# WatchSchematic.net
KiCad netlist of a schematic drawn in EAGLE
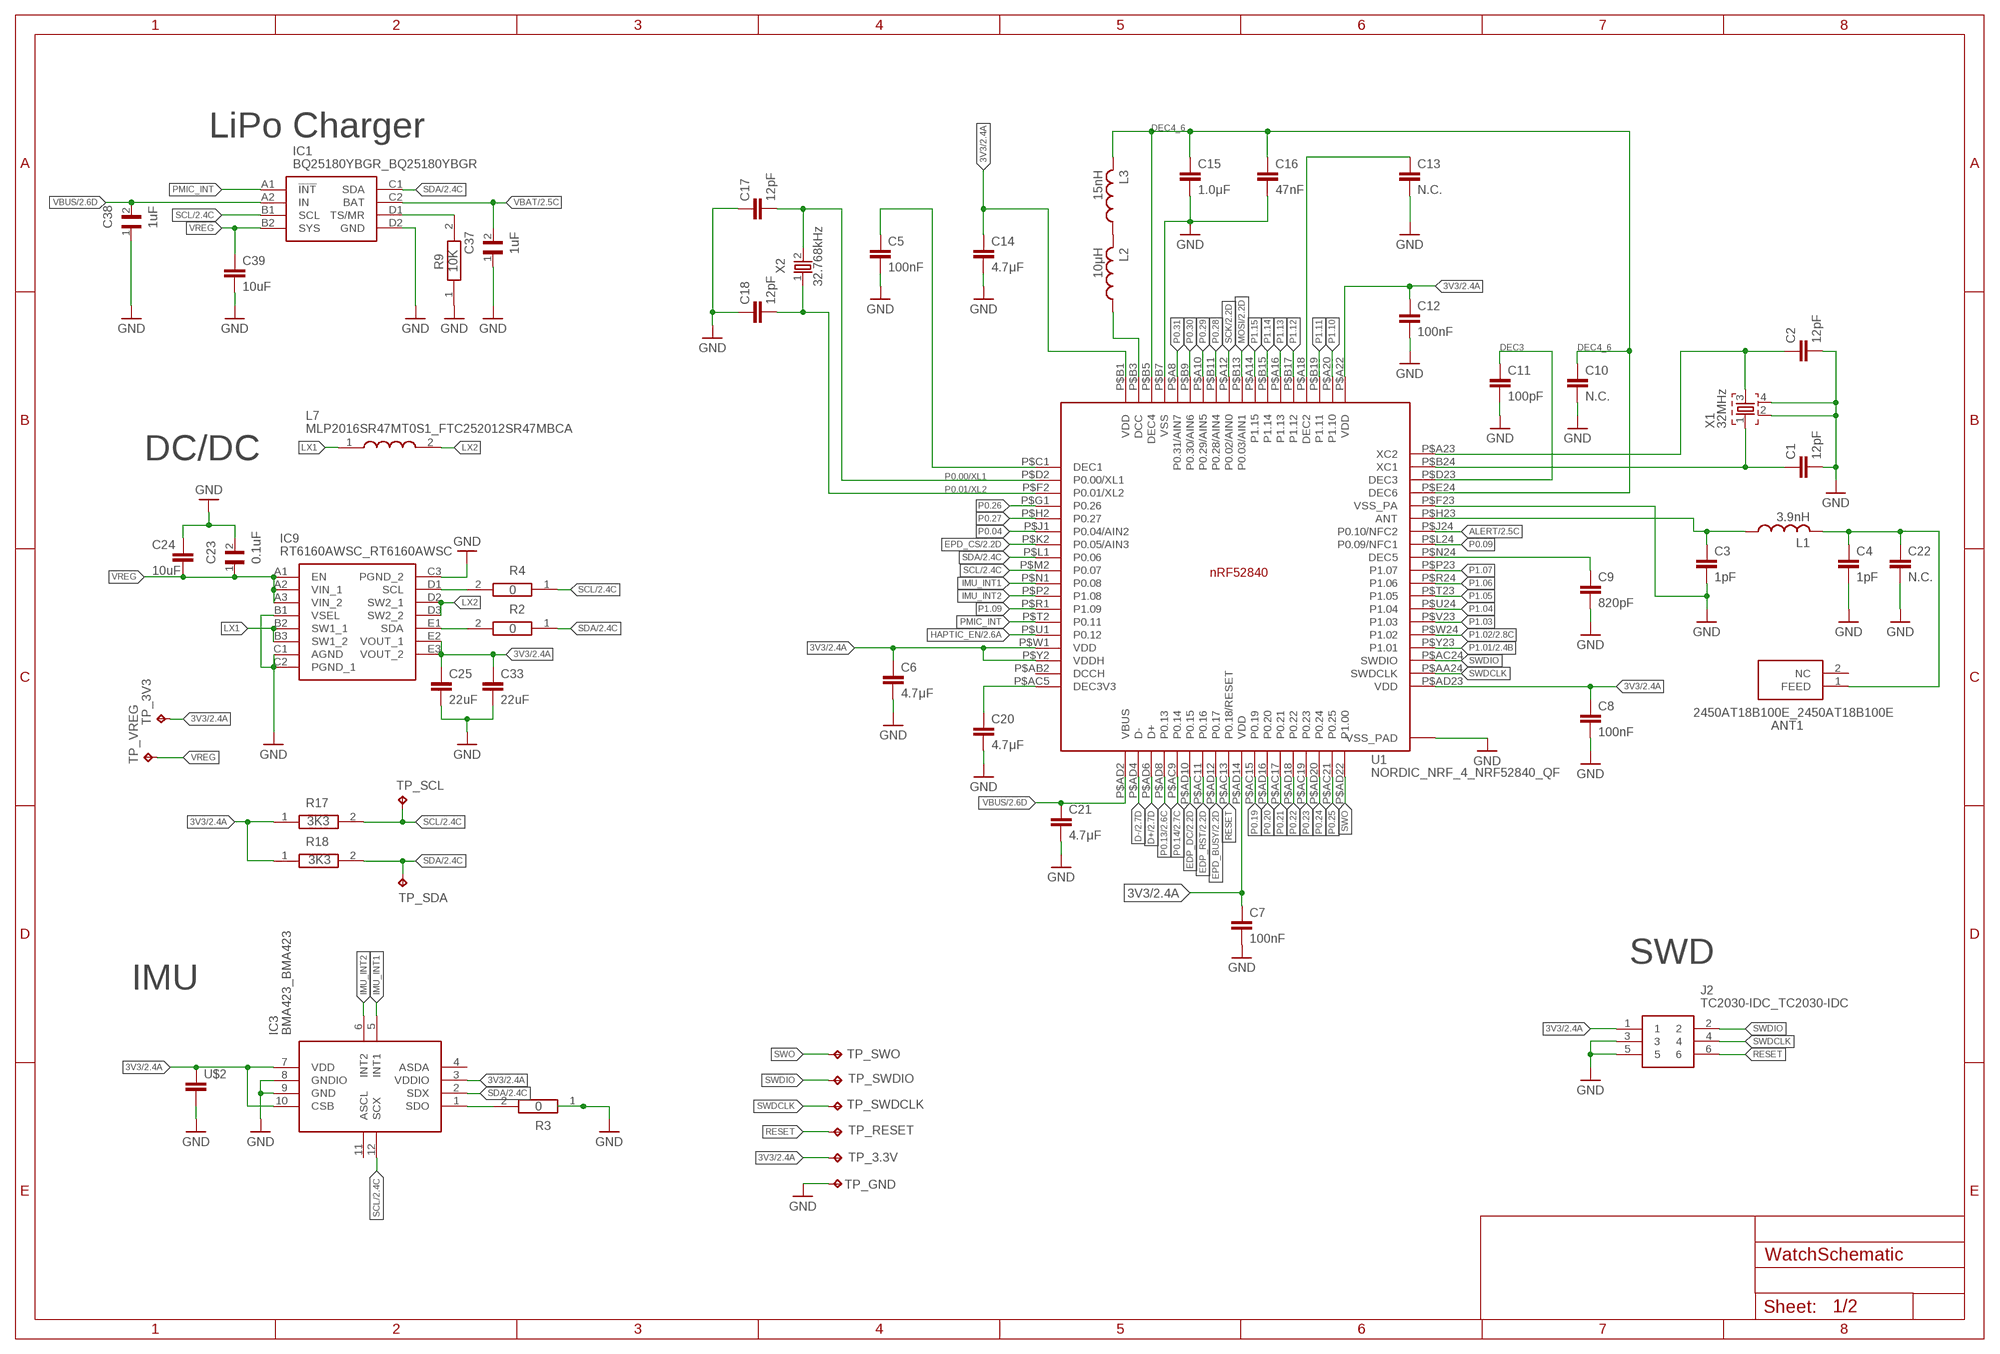
[diagram p0: schematic, sheet 1]
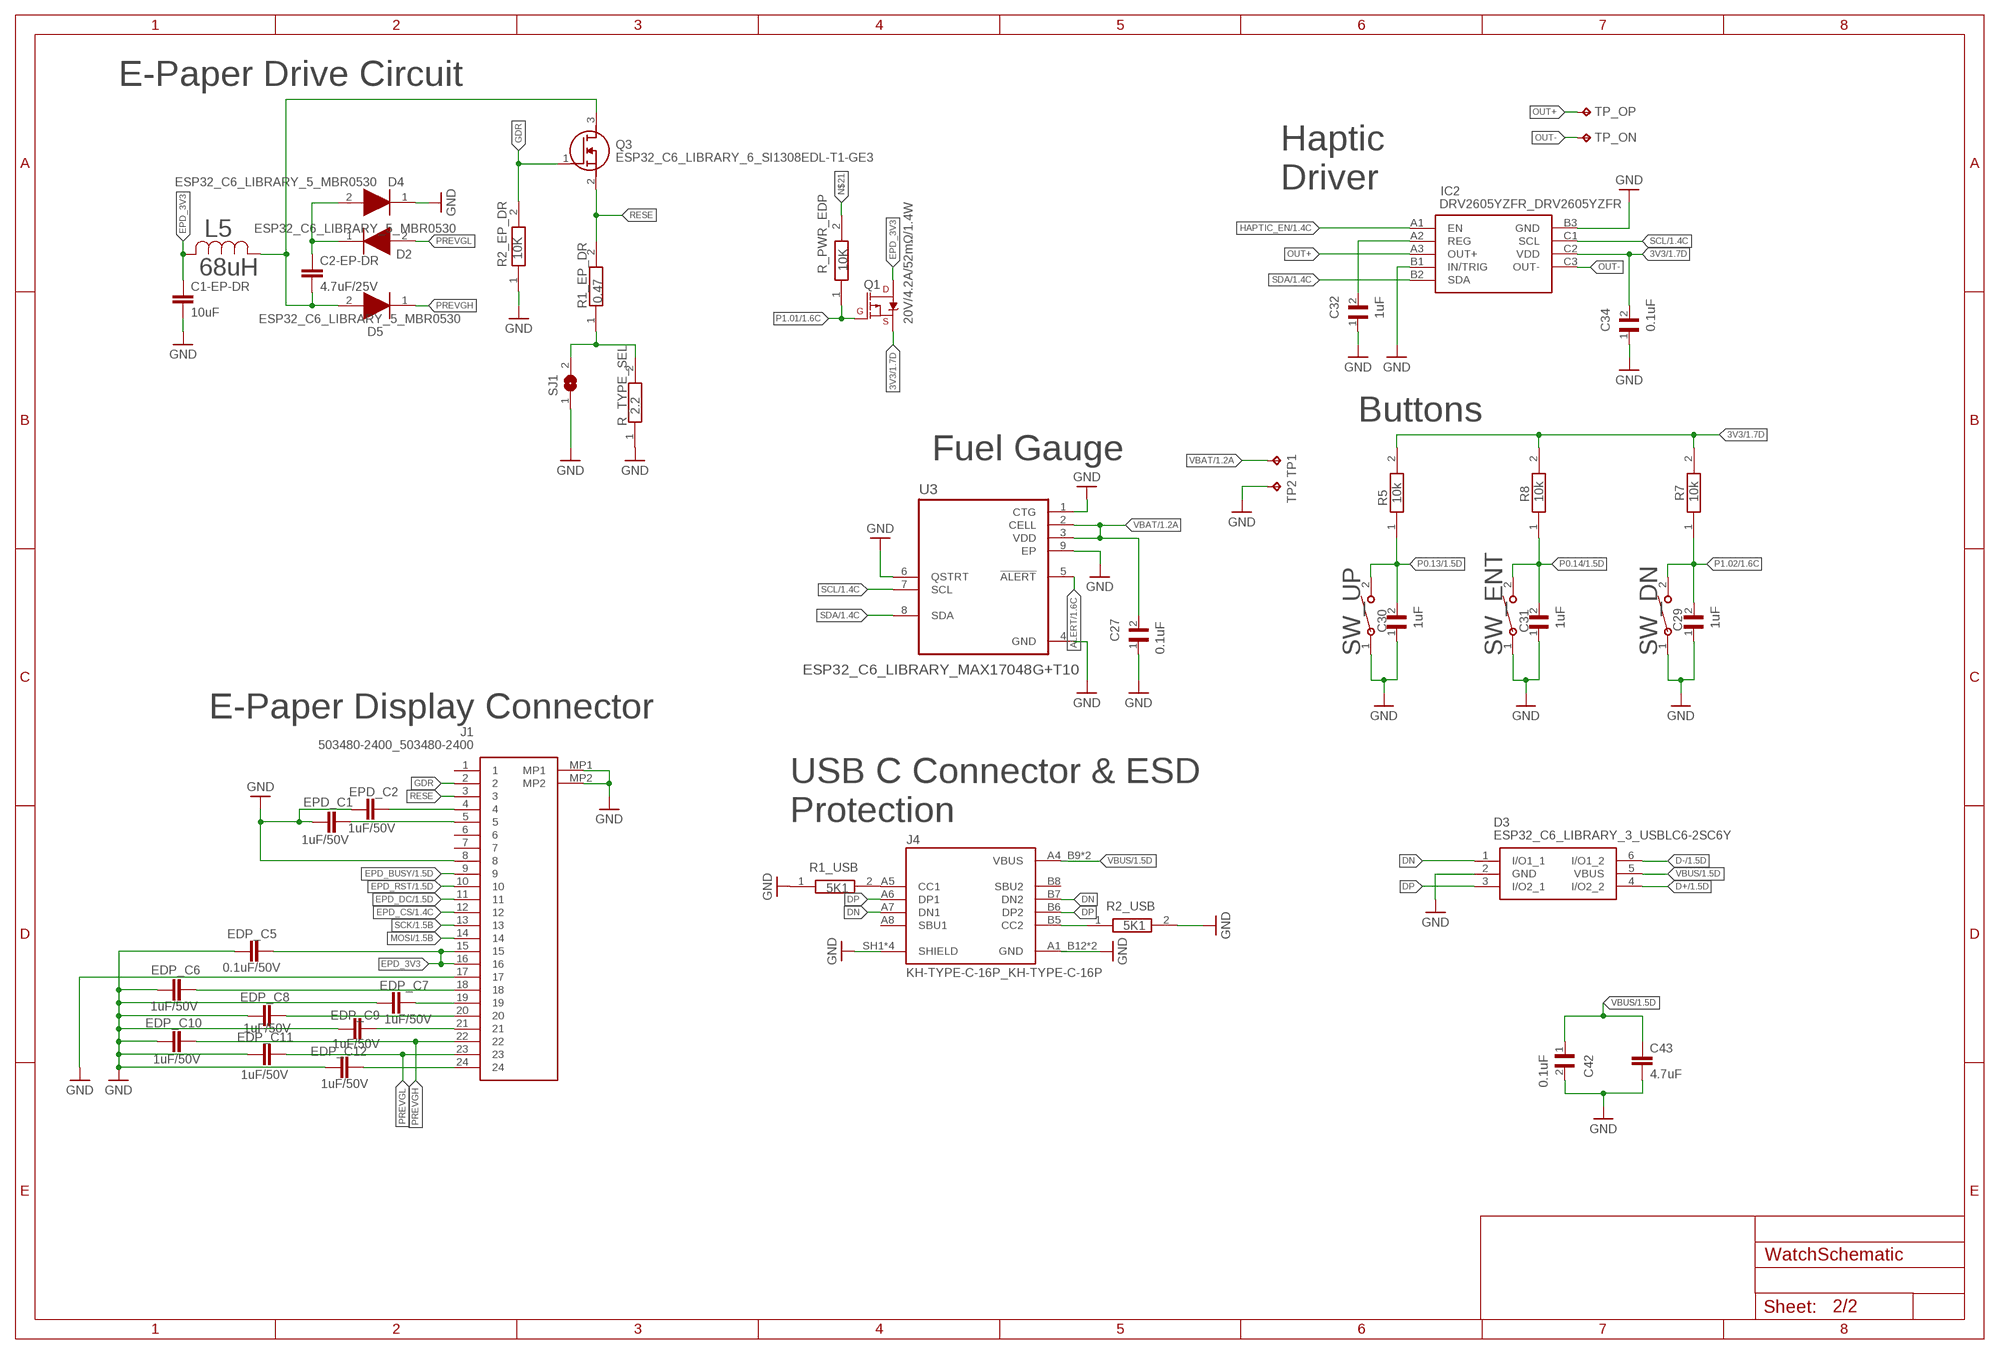
[diagram p1: schematic, sheet 2]

(export (version "E")
  (design (tool "Eeschema 10.0.6"))
  (components
    (comp (ref "ANT1")
      (value "2450AT18B100E_2450AT18B100E")
      (footprint "eagle-import:2450AT18B100E_ANTC3216X140N")
      (fields
        (field (name "ARROW_PART_NUMBER") "2450AT18B100E")
        (field (name "MOUSER_PART_NUMBER") "609-2450AT18B100E")
      )
      (libsource (lib "eagle-import") (part "2450AT18B100E_2450AT18B100E"))
    )
    (comp (ref "C1")
      (value "12pF")
      (footprint "eagle-import:NORDIC_NRF_3_RESC0201_L")
      (libsource (lib "eagle-import") (part "NORDIC_NRF_3_CAPACITOR_0201_L"))
    )
    (comp (ref "C2")
      (value "12pF")
      (footprint "eagle-import:NORDIC_NRF_3_RESC0201_L")
      (libsource (lib "eagle-import") (part "NORDIC_NRF_3_CAPACITOR_0201_L"))
    )
    (comp (ref "C3")
      (value "1pF")
      (footprint "eagle-import:NORDIC_NRF_3_RESC0201_L")
      (libsource (lib "eagle-import") (part "NORDIC_NRF_3_CAPACITOR_0201_L"))
    )
    (comp (ref "C4")
      (value "1pF")
      (footprint "eagle-import:NORDIC_NRF_3_RESC0201_L")
      (libsource (lib "eagle-import") (part "NORDIC_NRF_3_CAPACITOR_0201_L"))
    )
    (comp (ref "C5")
      (value "100nF")
      (footprint "eagle-import:NORDIC_NRF_3_RESC0201_L")
      (libsource (lib "eagle-import") (part "NORDIC_NRF_3_CAPACITOR_0201_L"))
    )
    (comp (ref "C6")
      (value "4.7μF")
      (footprint "eagle-import:NORDIC_NRF_3_RESC0201_L")
      (libsource (lib "eagle-import") (part "NORDIC_NRF_3_CAPACITOR_0201_L"))
    )
    (comp (ref "C7")
      (value "100nF")
      (footprint "eagle-import:NORDIC_NRF_3_RESC0201_L")
      (libsource (lib "eagle-import") (part "NORDIC_NRF_3_CAPACITOR_0201_L"))
    )
    (comp (ref "C8")
      (value "100nF")
      (footprint "eagle-import:NORDIC_NRF_3_RESC0201_L")
      (libsource (lib "eagle-import") (part "NORDIC_NRF_3_CAPACITOR_0201_L"))
    )
    (comp (ref "C9")
      (value "820pF")
      (footprint "eagle-import:NORDIC_NRF_3_RESC0201_L")
      (libsource (lib "eagle-import") (part "NORDIC_NRF_3_CAPACITOR_0201_L"))
    )
    (comp (ref "C10")
      (value "N.C.")
      (footprint "eagle-import:NORDIC_NRF_3_RESC0201_L")
      (libsource (lib "eagle-import") (part "NORDIC_NRF_3_CAPACITOR_0201_L"))
    )
    (comp (ref "C11")
      (value "100pF")
      (footprint "eagle-import:NORDIC_NRF_3_RESC0201_L")
      (libsource (lib "eagle-import") (part "NORDIC_NRF_3_CAPACITOR_0201_L"))
    )
    (comp (ref "C12")
      (value "100nF")
      (footprint "eagle-import:NORDIC_NRF_3_RESC0201_L")
      (libsource (lib "eagle-import") (part "NORDIC_NRF_3_CAPACITOR_0201_L"))
    )
    (comp (ref "C13")
      (value "N.C.")
      (footprint "eagle-import:NORDIC_NRF_3_RESC0201_L")
      (libsource (lib "eagle-import") (part "NORDIC_NRF_3_CAPACITOR_0201_L"))
    )
    (comp (ref "C14")
      (value "4.7μF")
      (footprint "eagle-import:NORDIC_NRF_3_RESC0201_L")
      (libsource (lib "eagle-import") (part "NORDIC_NRF_3_CAPACITOR_0201_L"))
    )
    (comp (ref "C15")
      (value "1.0μF")
      (footprint "eagle-import:NORDIC_NRF_3_RESC0201_L")
      (libsource (lib "eagle-import") (part "NORDIC_NRF_3_CAPACITOR_0201_L"))
    )
    (comp (ref "C16")
      (value "47nF")
      (footprint "eagle-import:NORDIC_NRF_3_RESC0201_L")
      (libsource (lib "eagle-import") (part "NORDIC_NRF_3_CAPACITOR_0201_L"))
    )
    (comp (ref "C17")
      (value "12pF")
      (footprint "eagle-import:NORDIC_NRF_3_RESC0201_L")
      (libsource (lib "eagle-import") (part "NORDIC_NRF_3_CAPACITOR_0201_L"))
    )
    (comp (ref "C18")
      (value "12pF")
      (footprint "eagle-import:NORDIC_NRF_3_RESC0201_L")
      (libsource (lib "eagle-import") (part "NORDIC_NRF_3_CAPACITOR_0201_L"))
    )
    (comp (ref "C20")
      (value "4.7μF")
      (footprint "eagle-import:NORDIC_NRF_3_RESC0201_L")
      (libsource (lib "eagle-import") (part "NORDIC_NRF_3_CAPACITOR_0201_L"))
    )
    (comp (ref "C21")
      (value "4.7μF")
      (footprint "eagle-import:NORDIC_NRF_3_RESC0201_L")
      (libsource (lib "eagle-import") (part "NORDIC_NRF_3_CAPACITOR_0201_L"))
    )
    (comp (ref "C22")
      (value "N.C.")
      (footprint "eagle-import:NORDIC_NRF_3_RESC0201_L")
      (libsource (lib "eagle-import") (part "NORDIC_NRF_3_CAPACITOR_0201_L"))
    )
    (comp (ref "C23")
      (value "0.1uF")
      (footprint "eagle-import:GRM011R60J152KE01L_1_0201")
      (libsource (lib "eagle-import") (part "GRM011R60J152KE01L_1_GRM011R60J152KE01L"))
    )
    (comp (ref "C24")
      (value "10uF")
      (footprint "eagle-import:NORDIC_NRF_3_RESC0201_L")
      (libsource (lib "eagle-import") (part "NORDIC_NRF_3_CAPACITOR_0201_L"))
    )
    (comp (ref "C25")
      (value "22uF")
      (footprint "eagle-import:NORDIC_NRF_3_RESC0201_L")
      (libsource (lib "eagle-import") (part "NORDIC_NRF_3_CAPACITOR_0201_L"))
    )
    (comp (ref "C33")
      (value "22uF")
      (footprint "eagle-import:NORDIC_NRF_3_RESC0201_L")
      (libsource (lib "eagle-import") (part "NORDIC_NRF_3_CAPACITOR_0201_L"))
    )
    (comp (ref "C37")
      (value "1uF")
      (footprint "eagle-import:GRM011R60J152KE01L_1_0201")
      (libsource (lib "eagle-import") (part "GRM011R60J152KE01L_1_GRM011R60J152KE01L"))
    )
    (comp (ref "C38")
      (value "1uF")
      (footprint "eagle-import:GRM011R60J152KE01L_1_0201")
      (libsource (lib "eagle-import") (part "GRM011R60J152KE01L_1_GRM011R60J152KE01L"))
    )
    (comp (ref "C39")
      (value "10uF")
      (footprint "eagle-import:NORDIC_NRF_3_RESC0201_L")
      (libsource (lib "eagle-import") (part "NORDIC_NRF_3_CAPACITOR_0201_L"))
    )
    (comp (ref "IC1")
      (value "BQ25180YBGR_BQ25180YBGR")
      (footprint "eagle-import:BQ25180YBGR_BGA8C40P2X4_100X155X50")
      (fields
        (field (name "ARROW_PART_NUMBER") "BQ25180YBGR")
        (field (name "MOUSER_PART_NUMBER") "595-BQ25180YBGR")
      )
      (libsource (lib "eagle-import") (part "BQ25180YBGR_BQ25180YBGR"))
    )
    (comp (ref "IC3")
      (value "BMA423_BMA423")
      (footprint "eagle-import:BMA423_BMA423")
      (fields (field (name "ARROW_PART_NUMBER") "BMA423") (field (name "MOUSER_PART_NUMBER") "262-BMA423"))
      (libsource (lib "eagle-import") (part "BMA423_BMA423"))
    )
    (comp (ref "IC9")
      (value "RT6160AWSC_RT6160AWSC")
      (footprint "eagle-import:RT6160AWSC_BGA15C40P3X5_140X230X60")
      (fields
        (field (name "MANUFACTURER_PART_NUMBER") "RT6160AWSC")
        (field (name "MOUSER_PART_NUMBER") "835-RT6160AWSC")
      )
      (libsource (lib "eagle-import") (part "RT6160AWSC_RT6160AWSC"))
    )
    (comp (ref "J2")
      (value "TC2030-IDC_TC2030-IDC")
      (footprint "eagle-import:TC2030-IDC_TC2030IDC")
      (fields (field (name "MANUFACTURER_PART_NUMBER") "TC2030-IDC"))
      (libsource (lib "eagle-import") (part "TC2030-IDC_TC2030-IDC"))
    )
    (comp (ref "L1")
      (value "3.9nH")
      (footprint "eagle-import:NORDIC_NRF_2_RESC0402_L")
      (libsource (lib "eagle-import") (part "NORDIC_NRF_2_INDUCTOR_0402_L"))
    )
    (comp (ref "L2")
      (value "10μH")
      (footprint "eagle-import:NORDIC_NRF_2_RESC0402_L")
      (libsource (lib "eagle-import") (part "NORDIC_NRF_2_INDUCTOR_0402_L"))
    )
    (comp (ref "L3")
      (value "15nH")
      (footprint "eagle-import:NORDIC_NRF_2_RESC0402_L")
      (libsource (lib "eagle-import") (part "NORDIC_NRF_2_INDUCTOR_0402_L"))
    )
    (comp (ref "L7")
      (value "MLP2016SR47MT0S1_FTC252012SR47MBCA")
      (footprint "eagle-import:MLP2016SR47MT0S1_INDC2016X100N")
      (fields (field (name "MANUFACTURER_PART_NUMBER") "FTC252012SR47MBCA"))
      (libsource (lib "eagle-import") (part "MLP2016SR47MT0S1_FTC252012SR47MBCA"))
    )
    (comp (ref "R2")
      (value "0")
      (footprint "eagle-import:CPF0201D7K68C1_0201")
      (libsource (lib "eagle-import") (part "CPF0201D7K68C1_CPF0201D7K68C1"))
    )
    (comp (ref "R3")
      (value "0")
      (footprint "eagle-import:CPF0201D7K68C1_0201")
      (libsource (lib "eagle-import") (part "CPF0201D7K68C1_CPF0201D7K68C1"))
    )
    (comp (ref "R4")
      (value "0")
      (footprint "eagle-import:CPF0201D7K68C1_0201")
      (libsource (lib "eagle-import") (part "CPF0201D7K68C1_CPF0201D7K68C1"))
    )
    (comp (ref "R9")
      (value "10K")
      (footprint "eagle-import:CPF0201D7K68C1_0201")
      (libsource (lib "eagle-import") (part "CPF0201D7K68C1_CPF0201D7K68C1"))
    )
    (comp (ref "R17")
      (value "3K3")
      (footprint "eagle-import:CPF0201D7K68C1_0201")
      (libsource (lib "eagle-import") (part "CPF0201D7K68C1_CPF0201D7K68C1"))
    )
    (comp (ref "R18")
      (value "3K3")
      (footprint "eagle-import:CPF0201D7K68C1_0201")
      (libsource (lib "eagle-import") (part "CPF0201D7K68C1_CPF0201D7K68C1"))
    )
    (comp (ref "TP_3.3V")
      (value "HECTOR_WATCH_1_TPTP20R")
      (footprint "eagle-import:HECTOR_WATCH_1_TP20R")
      (libsource (lib "eagle-import") (part "HECTOR_WATCH_1_TPTP20R"))
    )
    (comp (ref "TP_3V3")
      (value "HECTOR_WATCH_1_TPTP20R")
      (footprint "eagle-import:HECTOR_WATCH_1_TP20R")
      (libsource (lib "eagle-import") (part "HECTOR_WATCH_1_TPTP20R"))
    )
    (comp (ref "TP_GND")
      (value "HECTOR_WATCH_1_TPTP20R")
      (footprint "eagle-import:HECTOR_WATCH_1_TP20R")
      (libsource (lib "eagle-import") (part "HECTOR_WATCH_1_TPTP20R"))
    )
    (comp (ref "TP_RESET")
      (value "HECTOR_WATCH_1_TPTP20R")
      (footprint "eagle-import:HECTOR_WATCH_1_TP20R")
      (libsource (lib "eagle-import") (part "HECTOR_WATCH_1_TPTP20R"))
    )
    (comp (ref "TP_SCL")
      (value "HECTOR_WATCH_1_TPTP20R")
      (footprint "eagle-import:HECTOR_WATCH_1_TP20R")
      (libsource (lib "eagle-import") (part "HECTOR_WATCH_1_TPTP20R"))
    )
    (comp (ref "TP_SDA")
      (value "HECTOR_WATCH_1_TPTP20R")
      (footprint "eagle-import:HECTOR_WATCH_1_TP20R")
      (libsource (lib "eagle-import") (part "HECTOR_WATCH_1_TPTP20R"))
    )
    (comp (ref "TP_SWDCLK")
      (value "HECTOR_WATCH_1_TPTP20R")
      (footprint "eagle-import:HECTOR_WATCH_1_TP20R")
      (libsource (lib "eagle-import") (part "HECTOR_WATCH_1_TPTP20R"))
    )
    (comp (ref "TP_SWDIO")
      (value "HECTOR_WATCH_1_TPTP20R")
      (footprint "eagle-import:HECTOR_WATCH_1_TP20R")
      (libsource (lib "eagle-import") (part "HECTOR_WATCH_1_TPTP20R"))
    )
    (comp (ref "TP_SWO")
      (value "HECTOR_WATCH_1_TPTP20R")
      (footprint "eagle-import:HECTOR_WATCH_1_TP20R")
      (libsource (lib "eagle-import") (part "HECTOR_WATCH_1_TPTP20R"))
    )
    (comp (ref "TP_VREG")
      (value "HECTOR_WATCH_1_TPTP20R")
      (footprint "eagle-import:HECTOR_WATCH_1_TP20R")
      (libsource (lib "eagle-import") (part "HECTOR_WATCH_1_TPTP20R"))
    )
    (comp (ref "U$2")
      (value "NORDIC_NRF_3_CAPACITOR_0201_L")
      (footprint "eagle-import:NORDIC_NRF_3_RESC0201_L")
      (libsource (lib "eagle-import") (part "NORDIC_NRF_3_CAPACITOR_0201_L"))
    )
    (comp (ref "U1")
      (value "NORDIC_NRF_4_NRF52840_QF")
      (footprint "eagle-import:NORDIC_NRF_4_AQFN50P700X700X85_HS-74N")
      (libsource (lib "eagle-import") (part "NORDIC_NRF_4_NRF52840_QF"))
    )
    (comp (ref "X1")
      (value "32MHz")
      (footprint "eagle-import:NORDIC_NRF_BT-XTAL_2016_N")
      (libsource (lib "eagle-import") (part "NORDIC_NRF_XTAL_32MHZ"))
    )
    (comp (ref "X2")
      (value "32.768kHz")
      (footprint "eagle-import:NORDIC_NRF_1_XTAL_3215_N")
      (libsource (lib "eagle-import") (part "NORDIC_NRF_1_XTAL_32KHZ"))
    )
    (comp (ref "C1-EP-DR")
      (value "10uF")
      (footprint "eagle-import:NORDIC_NRF_3_RESC0201_L")
      (libsource (lib "eagle-import") (part "NORDIC_NRF_3_CAPACITOR_0201_L"))
    )
    (comp (ref "C2-EP-DR")
      (value "4.7uF/25V")
      (footprint "eagle-import:NORDIC_NRF_3_RESC0201_L")
      (libsource (lib "eagle-import") (part "NORDIC_NRF_3_CAPACITOR_0201_L"))
    )
    (comp (ref "C27")
      (value "0.1uF")
      (footprint "eagle-import:GRM011R60J152KE01L_1_0201")
      (libsource (lib "eagle-import") (part "GRM011R60J152KE01L_1_GRM011R60J152KE01L"))
    )
    (comp (ref "C29")
      (value "1uF")
      (footprint "eagle-import:GRM011R60J152KE01L_1_0201")
      (libsource (lib "eagle-import") (part "GRM011R60J152KE01L_1_GRM011R60J152KE01L"))
    )
    (comp (ref "C30")
      (value "1uF")
      (footprint "eagle-import:GRM011R60J152KE01L_1_0201")
      (libsource (lib "eagle-import") (part "GRM011R60J152KE01L_1_GRM011R60J152KE01L"))
    )
    (comp (ref "C31")
      (value "1uF")
      (footprint "eagle-import:GRM011R60J152KE01L_1_0201")
      (libsource (lib "eagle-import") (part "GRM011R60J152KE01L_1_GRM011R60J152KE01L"))
    )
    (comp (ref "C32")
      (value "1uF")
      (footprint "eagle-import:GRM011R60J152KE01L_1_0201")
      (libsource (lib "eagle-import") (part "GRM011R60J152KE01L_1_GRM011R60J152KE01L"))
    )
    (comp (ref "C34")
      (value "0.1uF")
      (footprint "eagle-import:GRM011R60J152KE01L_1_0201")
      (libsource (lib "eagle-import") (part "GRM011R60J152KE01L_1_GRM011R60J152KE01L"))
    )
    (comp (ref "C42")
      (value "0.1uF")
      (footprint "eagle-import:GRM011R60J152KE01L_1_0201")
      (libsource (lib "eagle-import") (part "GRM011R60J152KE01L_1_GRM011R60J152KE01L"))
    )
    (comp (ref "C43")
      (value "4.7uF")
      (footprint "eagle-import:NORDIC_NRF_3_RESC0201_L")
      (libsource (lib "eagle-import") (part "NORDIC_NRF_3_CAPACITOR_0201_L"))
    )
    (comp (ref "D2")
      (value "ESP32_C6_LIBRARY_5_MBR0530")
      (footprint "eagle-import:ESP32_C6_LIBRARY_5_SOD3716X135N")
      (fields (field (name "MF") "ON Semiconductor") (field (name "MP") "MBR0530"))
      (libsource (lib "eagle-import") (part "ESP32_C6_LIBRARY_5_MBR0530"))
    )
    (comp (ref "D3")
      (value "ESP32_C6_LIBRARY_3_USBLC6-2SC6Y")
      (footprint "eagle-import:ESP32_C6_LIBRARY_3_SOT95P280X145-6N")
      (fields (field (name "MF") "STMicroelectronics") (field (name "MP") "USBLC6-2SC6Y"))
      (libsource (lib "eagle-import") (part "ESP32_C6_LIBRARY_3_USBLC6-2SC6Y"))
    )
    (comp (ref "D4")
      (value "ESP32_C6_LIBRARY_5_MBR0530")
      (footprint "eagle-import:ESP32_C6_LIBRARY_5_SOD3716X135N")
      (fields (field (name "MF") "ON Semiconductor") (field (name "MP") "MBR0530"))
      (libsource (lib "eagle-import") (part "ESP32_C6_LIBRARY_5_MBR0530"))
    )
    (comp (ref "D5")
      (value "ESP32_C6_LIBRARY_5_MBR0530")
      (footprint "eagle-import:ESP32_C6_LIBRARY_5_SOD3716X135N")
      (fields (field (name "MF") "ON Semiconductor") (field (name "MP") "MBR0530"))
      (libsource (lib "eagle-import") (part "ESP32_C6_LIBRARY_5_MBR0530"))
    )
    (comp (ref "EDP_C5")
      (value "0.1uF/50V")
      (footprint "eagle-import:NORDIC_NRF_3_RESC0201_L")
      (libsource (lib "eagle-import") (part "NORDIC_NRF_3_CAPACITOR_0201_L"))
    )
    (comp (ref "EDP_C6")
      (value "1uF/50V")
      (footprint "eagle-import:NORDIC_NRF_3_RESC0201_L")
      (libsource (lib "eagle-import") (part "NORDIC_NRF_3_CAPACITOR_0201_L"))
    )
    (comp (ref "EDP_C7")
      (value "1uF/50V")
      (footprint "eagle-import:NORDIC_NRF_3_RESC0201_L")
      (libsource (lib "eagle-import") (part "NORDIC_NRF_3_CAPACITOR_0201_L"))
    )
    (comp (ref "EDP_C8")
      (value "1uF/50V")
      (footprint "eagle-import:NORDIC_NRF_3_RESC0201_L")
      (libsource (lib "eagle-import") (part "NORDIC_NRF_3_CAPACITOR_0201_L"))
    )
    (comp (ref "EDP_C9")
      (value "1uF/50V")
      (footprint "eagle-import:NORDIC_NRF_3_RESC0201_L")
      (libsource (lib "eagle-import") (part "NORDIC_NRF_3_CAPACITOR_0201_L"))
    )
    (comp (ref "EDP_C10")
      (value "1uF/50V")
      (footprint "eagle-import:NORDIC_NRF_3_RESC0201_L")
      (libsource (lib "eagle-import") (part "NORDIC_NRF_3_CAPACITOR_0201_L"))
    )
    (comp (ref "EDP_C11")
      (value "1uF/50V")
      (footprint "eagle-import:NORDIC_NRF_3_RESC0201_L")
      (libsource (lib "eagle-import") (part "NORDIC_NRF_3_CAPACITOR_0201_L"))
    )
    (comp (ref "EDP_C12")
      (value "1uF/50V")
      (footprint "eagle-import:NORDIC_NRF_3_RESC0201_L")
      (libsource (lib "eagle-import") (part "NORDIC_NRF_3_CAPACITOR_0201_L"))
    )
    (comp (ref "EPD_C1")
      (value "1uF/50V")
      (footprint "eagle-import:NORDIC_NRF_3_RESC0201_L")
      (libsource (lib "eagle-import") (part "NORDIC_NRF_3_CAPACITOR_0201_L"))
    )
    (comp (ref "EPD_C2")
      (value "1uF/50V")
      (footprint "eagle-import:NORDIC_NRF_3_RESC0201_L")
      (libsource (lib "eagle-import") (part "NORDIC_NRF_3_CAPACITOR_0201_L"))
    )
    (comp (ref "IC2")
      (value "DRV2605YZFR_DRV2605YZFR")
      (footprint "eagle-import:DRV2605YZFR_BGA9C50P3X3_144X144X62")
      (fields (field (name "ARROW_PART_NUMBER") "DRV2605YZFR"))
      (libsource (lib "eagle-import") (part "DRV2605YZFR_DRV2605YZFR"))
    )
    (comp (ref "J1")
      (value "503480-2400_503480-2400")
      (footprint "eagle-import:503480-2400_5034802400")
      (fields
        (field (name "MANUFACTURER_PART_NUMBER") "503480-2400")
        (field (name "MOUSER_PART_NUMBER") "538-503480-2400")
      )
      (libsource (lib "eagle-import") (part "503480-2400_503480-2400"))
    )
    (comp (ref "J4")
      (value "KH-TYPE-C-16P_KH-TYPE-C-16P")
      (footprint "eagle-import:KH-TYPE-C-16P_KINGHELM_KH-TYPE-C-16P")
      (fields (field (name "MF") "kinghelm") (field (name "MP") "KH-TYPE-C-16P"))
      (libsource (lib "eagle-import") (part "KH-TYPE-C-16P_KH-TYPE-C-16P"))
    )
    (comp (ref "L5")
      (value "68uH")
      (footprint "eagle-import:ESP32_C6_LIBRARY_2_IND_4828-WE-TPC_WRE")
      (fields
        (field (name "MANUFACTURER_PART_NUMBER") "744043680")
        (field (name "COPYRIGHT") "Copyright (C) 2024 Ultra Librarian. All rights reserved.")
      )
      (libsource (lib "eagle-import") (part "ESP32_C6_LIBRARY_2_744043680IND_4828-WE-TPC_WRE"))
    )
    (comp (ref "Q1")
      (value "20V/4.2A/52mΩ/1.4W")
      (footprint "eagle-import:ESP32_C6_LIBRARY_4_ESP32_C6_LIBRARY_4_ESP32_C6_LIBRARY_4_ESP32_C6_LIBRARY_4_ESP32_WROVER_SPARKFUN-DISCRETESEMI_SOT23-3")
      (libsource (lib "eagle-import") (part "ESP32_C6_LIBRARY_4_ESP32_WROVER_SPARKFUN-DISCRETESEMI_MOSFET_PCH-DMG2305UX-7"))
    )
    (comp (ref "Q3")
      (value "ESP32_C6_LIBRARY_6_SI1308EDL-T1-GE3")
      (footprint "eagle-import:ESP32_C6_LIBRARY_6_SOT65P210X110-3N")
      (fields (field (name "MF") "Vishay Siliconix") (field (name "MP") "SI1308EDL-T1-GE3"))
      (libsource (lib "eagle-import") (part "ESP32_C6_LIBRARY_6_SI1308EDL-T1-GE3"))
    )
    (comp (ref "R1_EP_DR")
      (value "0.47")
      (footprint "eagle-import:CPF0201D7K68C1_0201")
      (libsource (lib "eagle-import") (part "CPF0201D7K68C1_CPF0201D7K68C1"))
    )
    (comp (ref "R1_USB")
      (value "5K1")
      (footprint "eagle-import:CPF0201D7K68C1_0201")
      (libsource (lib "eagle-import") (part "CPF0201D7K68C1_CPF0201D7K68C1"))
    )
    (comp (ref "R2_EP_DR")
      (value "10K")
      (footprint "eagle-import:CPF0201D7K68C1_0201")
      (libsource (lib "eagle-import") (part "CPF0201D7K68C1_CPF0201D7K68C1"))
    )
    (comp (ref "R2_USB")
      (value "5K1")
      (footprint "eagle-import:CPF0201D7K68C1_0201")
      (libsource (lib "eagle-import") (part "CPF0201D7K68C1_CPF0201D7K68C1"))
    )
    (comp (ref "R5")
      (value "10k")
      (footprint "eagle-import:CPF0201D7K68C1_0201")
      (libsource (lib "eagle-import") (part "CPF0201D7K68C1_CPF0201D7K68C1"))
    )
    (comp (ref "R7")
      (value "10k")
      (footprint "eagle-import:CPF0201D7K68C1_0201")
      (libsource (lib "eagle-import") (part "CPF0201D7K68C1_CPF0201D7K68C1"))
    )
    (comp (ref "R8")
      (value "10k")
      (footprint "eagle-import:CPF0201D7K68C1_0201")
      (libsource (lib "eagle-import") (part "CPF0201D7K68C1_CPF0201D7K68C1"))
    )
    (comp (ref "R_PWR_EDP")
      (value "10K")
      (footprint "eagle-import:CPF0201D7K68C1_0201")
      (libsource (lib "eagle-import") (part "CPF0201D7K68C1_CPF0201D7K68C1"))
    )
    (comp (ref "R_TYPE_SEL")
      (value "2.2")
      (footprint "eagle-import:CPF0201D7K68C1_0201")
      (libsource (lib "eagle-import") (part "CPF0201D7K68C1_CPF0201D7K68C1"))
    )
    (comp (ref "SJ1")
      (value "ESP32_C6_LIBRARY_7_JUMPER_SJ")
      (footprint "eagle-import:ESP32_C6_LIBRARY_7_JUMPER_SJ")
      (libsource (lib "eagle-import") (part "ESP32_C6_LIBRARY_7_JUMPER_SJ"))
    )
    (comp (ref "SW_DN")
      (value "2025-10-22_07-23-44_LIBRARY_EVP-AKE31ASW_EVP-AKE31A_PAN")
      (footprint "eagle-import:2025-10-22_07-23-44_LIBRARY_SW_EVP-AKE31A_PAN")
      (fields
        (field (name "MANUFACTURER_PART_NUMBER") "EVP-AKE31A")
        (field (name "COPYRIGHT") "Copyright (C) 2025 Ultra Librarian. All rights reserved.")
      )
      (libsource (lib "eagle-import") (part "2025-10-22_07-23-44_LIBRARY_EVP-AKE31ASW_EVP-AKE31A_PAN"))
    )
    (comp (ref "SW_ENT")
      (value "2025-10-22_07-23-44_LIBRARY_EVP-AKE31ASW_EVP-AKE31A_PAN")
      (footprint "eagle-import:2025-10-22_07-23-44_LIBRARY_SW_EVP-AKE31A_PAN")
      (fields
        (field (name "MANUFACTURER_PART_NUMBER") "EVP-AKE31A")
        (field (name "COPYRIGHT") "Copyright (C) 2025 Ultra Librarian. All rights reserved.")
      )
      (libsource (lib "eagle-import") (part "2025-10-22_07-23-44_LIBRARY_EVP-AKE31ASW_EVP-AKE31A_PAN"))
    )
    (comp (ref "SW_UP")
      (value "2025-10-22_07-23-44_LIBRARY_EVP-AKE31ASW_EVP-AKE31A_PAN")
      (footprint "eagle-import:2025-10-22_07-23-44_LIBRARY_SW_EVP-AKE31A_PAN")
      (fields
        (field (name "MANUFACTURER_PART_NUMBER") "EVP-AKE31A")
        (field (name "COPYRIGHT") "Copyright (C) 2025 Ultra Librarian. All rights reserved.")
      )
      (libsource (lib "eagle-import") (part "2025-10-22_07-23-44_LIBRARY_EVP-AKE31ASW_EVP-AKE31A_PAN"))
    )
    (comp (ref "TP1")
      (value "HECTOR_WATCH_1_TPTP20R")
      (footprint "eagle-import:HECTOR_WATCH_1_TP20R")
      (libsource (lib "eagle-import") (part "HECTOR_WATCH_1_TPTP20R"))
    )
    (comp (ref "TP2")
      (value "HECTOR_WATCH_1_TPTP20R")
      (footprint "eagle-import:HECTOR_WATCH_1_TP20R")
      (libsource (lib "eagle-import") (part "HECTOR_WATCH_1_TPTP20R"))
    )
    (comp (ref "TP_ON")
      (value "HECTOR_WATCH_1_TPTP20R")
      (footprint "eagle-import:HECTOR_WATCH_1_TP20R")
      (libsource (lib "eagle-import") (part "HECTOR_WATCH_1_TPTP20R"))
    )
    (comp (ref "TP_OP")
      (value "HECTOR_WATCH_1_TPTP20R")
      (footprint "eagle-import:HECTOR_WATCH_1_TP20R")
      (libsource (lib "eagle-import") (part "HECTOR_WATCH_1_TPTP20R"))
    )
    (comp (ref "U3")
      (value "ESP32_C6_LIBRARY_MAX17048G+T10")
      (footprint "eagle-import:ESP32_C6_LIBRARY_SON50P200X200X80-9N")
      (fields (field (name "MF") "Analog Devices") (field (name "MP") "MAX17048G+T10"))
      (libsource (lib "eagle-import") (part "ESP32_C6_LIBRARY_MAX17048G+T10"))
    )
  )
  (nets
    (net (code "1") (name "3V3{slash}1.7D") (class "Default")
      (node (ref "C34") (pin "2") (pinfunction "2_2") (pintype "passive"))
      (node (ref "IC2") (pin "C2") (pinfunction "VDD_C2") (pintype "bidirectional"))
      (node (ref "Q1") (pin "2") (pinfunction "S_2") (pintype "bidirectional"))
      (node (ref "R5") (pin "2") (pinfunction "2_2") (pintype "bidirectional"))
      (node (ref "R7") (pin "2") (pinfunction "2_2") (pintype "bidirectional"))
      (node (ref "R8") (pin "2") (pinfunction "2_2") (pintype "bidirectional"))
    )
    (net (code "2") (name "3V3{slash}2.4A") (class "Default")
      (node (ref "C12") (pin "1") (pinfunction "1_1") (pintype "passive"))
      (node (ref "C14") (pin "1") (pinfunction "1_1") (pintype "passive"))
      (node (ref "C25") (pin "1") (pinfunction "1_1") (pintype "passive"))
      (node (ref "C33") (pin "1") (pinfunction "1_1") (pintype "passive"))
      (node (ref "C6") (pin "1") (pinfunction "1_1") (pintype "passive"))
      (node (ref "C7") (pin "1") (pinfunction "1_1") (pintype "passive"))
      (node (ref "C8") (pin "1") (pinfunction "1_1") (pintype "passive"))
      (node (ref "IC3") (pin "10") (pinfunction "CSB_10") (pintype "bidirectional"))
      (node (ref "IC3") (pin "3") (pinfunction "VDDIO_3") (pintype "bidirectional"))
      (node (ref "IC3") (pin "7") (pinfunction "VDD_7") (pintype "bidirectional"))
      (node (ref "IC9") (pin "E2") (pinfunction "VOUT_1_E2") (pintype "bidirectional"))
      (node (ref "IC9") (pin "E3") (pinfunction "VOUT_2_E3") (pintype "bidirectional"))
      (node (ref "J2") (pin "1") (pinfunction "1_1") (pintype "bidirectional"))
      (node (ref "R17") (pin "1") (pinfunction "1_1") (pintype "bidirectional"))
      (node (ref "R18") (pin "1") (pinfunction "1_1") (pintype "bidirectional"))
      (node (ref "TP_3.3V") (pin "TP") (pinfunction "TP_TP") (pintype "input"))
      (node (ref "TP_3V3") (pin "TP") (pinfunction "TP_TP") (pintype "input"))
      (node (ref "U$2") (pin "1") (pinfunction "1_1") (pintype "passive"))
      (node (ref "U1") (pin "P$A22") (pinfunction "VDD_P$A22") (pintype "power_in"))
      (node (ref "U1") (pin "P$AD14") (pinfunction "VDD_P$AD14") (pintype "power_in"))
      (node (ref "U1") (pin "P$AD23") (pinfunction "VDD_P$AD23") (pintype "power_in"))
      (node (ref "U1") (pin "P$B1") (pinfunction "VDD_P$B1") (pintype "power_in"))
      (node (ref "U1") (pin "P$W1") (pinfunction "VDD_P$W1") (pintype "power_in"))
      (node (ref "U1") (pin "P$Y2") (pinfunction "VDDH_P$Y2") (pintype "power_in"))
    )
    (net (code "3") (name "ALERT{slash}1.6C") (class "Default")
      (node (ref "U3") (pin "5") (pinfunction "~{ALERT}_5") (pintype "output"))
    )
    (net (code "4") (name "ALERT{slash}2.5C") (class "Default")
      (node (ref "U1") (pin "P$J24") (pinfunction "P0.10/NFC2_P$J24") (pintype "bidirectional"))
    )
    (net (code "5") (name "D+{slash}1.5D") (class "Default")
      (node (ref "D3") (pin "4") (pinfunction "I/O2_2_4") (pintype "bidirectional"))
    )
    (net (code "6") (name "D+{slash}2.7D") (class "Default")
      (node (ref "U1") (pin "P$AD6") (pinfunction "D+_P$AD6") (pintype "bidirectional"))
    )
    (net (code "7") (name "D-{slash}1.5D") (class "Default")
      (node (ref "D3") (pin "6") (pinfunction "I/O1_2_6") (pintype "bidirectional"))
    )
    (net (code "8") (name "D-{slash}2.7D") (class "Default")
      (node (ref "U1") (pin "P$AD4") (pinfunction "D-_P$AD4") (pintype "bidirectional"))
    )
    (net (code "9") (name "DEC3") (class "Default")
      (node (ref "C11") (pin "1") (pinfunction "1_1") (pintype "passive"))
      (node (ref "U1") (pin "P$D23") (pinfunction "DEC3_P$D23") (pintype "bidirectional"))
    )
    (net (code "10") (name "DEC4_6") (class "Default")
      (node (ref "C10") (pin "1") (pinfunction "1_1") (pintype "passive"))
      (node (ref "C15") (pin "1") (pinfunction "1_1") (pintype "passive"))
      (node (ref "C16") (pin "1") (pinfunction "1_1") (pintype "passive"))
      (node (ref "L3") (pin "2") (pinfunction "2_2") (pintype "passive"))
      (node (ref "U1") (pin "P$B5") (pinfunction "DEC4_P$B5") (pintype "power_in"))
      (node (ref "U1") (pin "P$E24") (pinfunction "DEC6_P$E24") (pintype "bidirectional"))
    )
    (net (code "11") (name "DN") (class "Default")
      (node (ref "D3") (pin "1") (pinfunction "I/O1_1_1") (pintype "bidirectional"))
      (node (ref "J4") (pin "A7") (pinfunction "DN1_A7") (pintype "bidirectional"))
      (node (ref "J4") (pin "B7") (pinfunction "DN2_B7") (pintype "bidirectional"))
    )
    (net (code "12") (name "DP") (class "Default")
      (node (ref "D3") (pin "3") (pinfunction "I/O2_1_3") (pintype "bidirectional"))
      (node (ref "J4") (pin "A6") (pinfunction "DP1_A6") (pintype "bidirectional"))
      (node (ref "J4") (pin "B6") (pinfunction "DP2_B6") (pintype "bidirectional"))
    )
    (net (code "13") (name "EDP_DC{slash}2.2D") (class "Default")
      (node (ref "U1") (pin "P$AD10") (pinfunction "P0.15_P$AD10") (pintype "bidirectional"))
    )
    (net (code "14") (name "EDP_RST{slash}2.2D") (class "Default")
      (node (ref "U1") (pin "P$AC11") (pinfunction "P0.16_P$AC11") (pintype "bidirectional"))
    )
    (net (code "15") (name "EPD_3V3") (class "Default")
      (node (ref "C1-EP-DR") (pin "1") (pinfunction "1_1") (pintype "passive"))
      (node (ref "EDP_C5") (pin "2") (pinfunction "2_2") (pintype "passive"))
      (node (ref "J1") (pin "15") (pinfunction "15_15") (pintype "bidirectional"))
      (node (ref "J1") (pin "16") (pinfunction "16_16") (pintype "bidirectional"))
      (node (ref "L5") (pin "2") (pinfunction "2_2") (pintype "passive"))
      (node (ref "Q1") (pin "3") (pinfunction "D_3") (pintype "bidirectional"))
    )
    (net (code "16") (name "EPD_BUSY{slash}1.5D") (class "Default")
      (node (ref "J1") (pin "9") (pinfunction "9_9") (pintype "bidirectional"))
    )
    (net (code "17") (name "EPD_BUSY{slash}2.2D") (class "Default")
      (node (ref "U1") (pin "P$AD12") (pinfunction "P0.17_P$AD12") (pintype "bidirectional"))
    )
    (net (code "18") (name "EPD_CS{slash}1.4C") (class "Default")
      (node (ref "J1") (pin "12") (pinfunction "12_12") (pintype "bidirectional"))
    )
    (net (code "19") (name "EPD_CS{slash}2.2D") (class "Default")
      (node (ref "U1") (pin "P$K2") (pinfunction "P0.05/AIN3_P$K2") (pintype "bidirectional"))
    )
    (net (code "20") (name "EPD_DC{slash}1.5D") (class "Default")
      (node (ref "J1") (pin "11") (pinfunction "11_11") (pintype "bidirectional"))
    )
    (net (code "21") (name "EPD_RST{slash}1.5D") (class "Default")
      (node (ref "J1") (pin "10") (pinfunction "10_10") (pintype "bidirectional"))
    )
    (net (code "22") (name "GDR") (class "Default")
      (node (ref "J1") (pin "2") (pinfunction "2_2") (pintype "bidirectional"))
      (node (ref "Q3") (pin "1") (pinfunction "G_1") (pintype "bidirectional"))
      (node (ref "R2_EP_DR") (pin "2") (pinfunction "2_2") (pintype "bidirectional"))
    )
    (net (code "23") (name "GND") (class "Default")
      (node (ref "C1") (pin "2") (pinfunction "2_2") (pintype "passive"))
      (node (ref "C1-EP-DR") (pin "2") (pinfunction "2_2") (pintype "passive"))
      (node (ref "C10") (pin "2") (pinfunction "2_2") (pintype "passive"))
      (node (ref "C11") (pin "2") (pinfunction "2_2") (pintype "passive"))
      (node (ref "C12") (pin "2") (pinfunction "2_2") (pintype "passive"))
      (node (ref "C13") (pin "2") (pinfunction "2_2") (pintype "passive"))
      (node (ref "C14") (pin "2") (pinfunction "2_2") (pintype "passive"))
      (node (ref "C15") (pin "2") (pinfunction "2_2") (pintype "passive"))
      (node (ref "C16") (pin "2") (pinfunction "2_2") (pintype "passive"))
      (node (ref "C17") (pin "1") (pinfunction "1_1") (pintype "passive"))
      (node (ref "C18") (pin "1") (pinfunction "1_1") (pintype "passive"))
      (node (ref "C2") (pin "2") (pinfunction "2_2") (pintype "passive"))
      (node (ref "C20") (pin "2") (pinfunction "2_2") (pintype "passive"))
      (node (ref "C21") (pin "2") (pinfunction "2_2") (pintype "passive"))
      (node (ref "C22") (pin "2") (pinfunction "2_2") (pintype "passive"))
      (node (ref "C23") (pin "2") (pinfunction "2_2") (pintype "passive"))
      (node (ref "C24") (pin "1") (pinfunction "1_1") (pintype "passive"))
      (node (ref "C25") (pin "2") (pinfunction "2_2") (pintype "passive"))
      (node (ref "C27") (pin "1") (pinfunction "1_1") (pintype "passive"))
      (node (ref "C29") (pin "1") (pinfunction "1_1") (pintype "passive"))
      (node (ref "C3") (pin "2") (pinfunction "2_2") (pintype "passive"))
      (node (ref "C30") (pin "1") (pinfunction "1_1") (pintype "passive"))
      (node (ref "C31") (pin "1") (pinfunction "1_1") (pintype "passive"))
      (node (ref "C32") (pin "1") (pinfunction "1_1") (pintype "passive"))
      (node (ref "C33") (pin "2") (pinfunction "2_2") (pintype "passive"))
      (node (ref "C34") (pin "1") (pinfunction "1_1") (pintype "passive"))
      (node (ref "C37") (pin "1") (pinfunction "1_1") (pintype "passive"))
      (node (ref "C38") (pin "1") (pinfunction "1_1") (pintype "passive"))
      (node (ref "C39") (pin "2") (pinfunction "2_2") (pintype "passive"))
      (node (ref "C4") (pin "2") (pinfunction "2_2") (pintype "passive"))
      (node (ref "C42") (pin "2") (pinfunction "2_2") (pintype "passive"))
      (node (ref "C43") (pin "2") (pinfunction "2_2") (pintype "passive"))
      (node (ref "C5") (pin "2") (pinfunction "2_2") (pintype "passive"))
      (node (ref "C6") (pin "2") (pinfunction "2_2") (pintype "passive"))
      (node (ref "C7") (pin "2") (pinfunction "2_2") (pintype "passive"))
      (node (ref "C8") (pin "2") (pinfunction "2_2") (pintype "passive"))
      (node (ref "C9") (pin "2") (pinfunction "2_2") (pintype "passive"))
      (node (ref "D3") (pin "2") (pinfunction "GND_2") (pintype "bidirectional"))
      (node (ref "D4") (pin "1") (pinfunction "K_1") (pintype "bidirectional"))
      (node (ref "EDP_C10") (pin "1") (pinfunction "1_1") (pintype "passive"))
      (node (ref "EDP_C11") (pin "1") (pinfunction "1_1") (pintype "passive"))
      (node (ref "EDP_C12") (pin "1") (pinfunction "1_1") (pintype "passive"))
      (node (ref "EDP_C5") (pin "1") (pinfunction "1_1") (pintype "passive"))
      (node (ref "EDP_C6") (pin "1") (pinfunction "1_1") (pintype "passive"))
      (node (ref "EDP_C7") (pin "1") (pinfunction "1_1") (pintype "passive"))
      (node (ref "EDP_C8") (pin "1") (pinfunction "1_1") (pintype "passive"))
      (node (ref "EDP_C9") (pin "1") (pinfunction "1_1") (pintype "passive"))
      (node (ref "EPD_C1") (pin "1") (pinfunction "1_1") (pintype "passive"))
      (node (ref "EPD_C2") (pin "1") (pinfunction "1_1") (pintype "passive"))
      (node (ref "IC1") (pin "D2") (pinfunction "GND_D2") (pintype "bidirectional"))
      (node (ref "IC2") (pin "B1") (pinfunction "IN/TRIG_B1") (pintype "bidirectional"))
      (node (ref "IC2") (pin "B3") (pinfunction "GND_B3") (pintype "bidirectional"))
      (node (ref "IC3") (pin "8") (pinfunction "GNDIO_8") (pintype "bidirectional"))
      (node (ref "IC3") (pin "9") (pinfunction "GND_9") (pintype "bidirectional"))
      (node (ref "IC9") (pin "B1") (pinfunction "VSEL_B1") (pintype "bidirectional"))
      (node (ref "IC9") (pin "C1") (pinfunction "AGND_C1") (pintype "bidirectional"))
      (node (ref "IC9") (pin "C2") (pinfunction "PGND_1_C2") (pintype "bidirectional"))
      (node (ref "IC9") (pin "C3") (pinfunction "PGND_2_C3") (pintype "bidirectional"))
      (node (ref "J1") (pin "17") (pinfunction "17_17") (pintype "bidirectional"))
      (node (ref "J1") (pin "8") (pinfunction "8_8") (pintype "bidirectional"))
      (node (ref "J1") (pin "MP1") (pinfunction "MP1_MP1") (pintype "bidirectional"))
      (node (ref "J1") (pin "MP2") (pinfunction "MP2_MP2") (pintype "bidirectional"))
      (node (ref "J2") (pin "3") (pinfunction "3_3") (pintype "bidirectional"))
      (node (ref "J2") (pin "5") (pinfunction "5_5") (pintype "bidirectional"))
      (node (ref "J4") (pin "A12_B1") (pinfunction "GND_A12_B1") (pintype "power_in"))
      (node (ref "J4") (pin "A1_B12") (pinfunction "GND_A1_B12") (pintype "power_in"))
      (node (ref "J4") (pin "SH1") (pinfunction "SHIELD_SH1") (pintype "passive"))
      (node (ref "J4") (pin "SH2") (pinfunction "SHIELD_SH2") (pintype "passive"))
      (node (ref "J4") (pin "SH3") (pinfunction "SHIELD_SH3") (pintype "passive"))
      (node (ref "J4") (pin "SH4") (pinfunction "SHIELD_SH4") (pintype "passive"))
      (node (ref "R1_USB") (pin "1") (pinfunction "1_1") (pintype "bidirectional"))
      (node (ref "R2_EP_DR") (pin "1") (pinfunction "1_1") (pintype "bidirectional"))
      (node (ref "R2_USB") (pin "2") (pinfunction "2_2") (pintype "bidirectional"))
      (node (ref "R3") (pin "1") (pinfunction "1_1") (pintype "bidirectional"))
      (node (ref "R9") (pin "1") (pinfunction "1_1") (pintype "bidirectional"))
      (node (ref "R_TYPE_SEL") (pin "1") (pinfunction "1_1") (pintype "bidirectional"))
      (node (ref "SJ1") (pin "1") (pinfunction "1_1") (pintype "passive"))
      (node (ref "SW_DN") (pin "1") (pinfunction "1_1") (pintype "passive"))
      (node (ref "SW_ENT") (pin "1") (pinfunction "1_1") (pintype "passive"))
      (node (ref "SW_UP") (pin "1") (pinfunction "1_1") (pintype "passive"))
      (node (ref "TP2") (pin "TP") (pinfunction "TP_TP") (pintype "input"))
      (node (ref "TP_GND") (pin "TP") (pinfunction "TP_TP") (pintype "input"))
      (node (ref "U$2") (pin "2") (pinfunction "2_2") (pintype "passive"))
      (node (ref "U1") (pin "P$74") (pinfunction "VSS_PAD_P$74") (pintype "bidirectional"))
      (node (ref "U1") (pin "P$75") (pinfunction "VSS_PAD_P$75") (pintype "bidirectional"))
      (node (ref "U1") (pin "P$76") (pinfunction "VSS_PAD_P$76") (pintype "bidirectional"))
      (node (ref "U1") (pin "P$77") (pinfunction "VSS_PAD_P$77") (pintype "bidirectional"))
      (node (ref "U1") (pin "P$78") (pinfunction "VSS_PAD_P$78") (pintype "bidirectional"))
      (node (ref "U1") (pin "P$79") (pinfunction "VSS_PAD_P$79") (pintype "bidirectional"))
      (node (ref "U1") (pin "P$80") (pinfunction "VSS_PAD_P$80") (pintype "bidirectional"))
      (node (ref "U1") (pin "P$81") (pinfunction "VSS_PAD_P$81") (pintype "bidirectional"))
      (node (ref "U1") (pin "P$82") (pinfunction "VSS_PAD_P$82") (pintype "bidirectional"))
      (node (ref "U1") (pin "P$83") (pinfunction "VSS_PAD_P$83") (pintype "bidirectional"))
      (node (ref "U1") (pin "P$84") (pinfunction "VSS_PAD_P$84") (pintype "bidirectional"))
      (node (ref "U1") (pin "P$85") (pinfunction "VSS_PAD_P$85") (pintype "bidirectional"))
      (node (ref "U1") (pin "P$86") (pinfunction "VSS_PAD_P$86") (pintype "bidirectional"))
      (node (ref "U1") (pin "P$87") (pinfunction "VSS_PAD_P$87") (pintype "bidirectional"))
      (node (ref "U1") (pin "P$88") (pinfunction "VSS_PAD_P$88") (pintype "bidirectional"))
      (node (ref "U1") (pin "P$89") (pinfunction "VSS_PAD_P$89") (pintype "bidirectional"))
      (node (ref "U1") (pin "P$90") (pinfunction "VSS_PAD_P$90") (pintype "bidirectional"))
      (node (ref "U1") (pin "P$B7") (pinfunction "VSS_P$B7") (pintype "power_in"))
      (node (ref "U1") (pin "P$F23") (pinfunction "VSS_PA_P$F23") (pintype "bidirectional"))
      (node (ref "U3") (pin "1") (pinfunction "CTG_1") (pintype "power_in"))
      (node (ref "U3") (pin "4") (pinfunction "GND_4") (pintype "power_in"))
      (node (ref "U3") (pin "6") (pinfunction "QSTRT_6") (pintype "input"))
      (node (ref "U3") (pin "9") (pinfunction "EP_9") (pintype "power_in"))
      (node (ref "X1") (pin "2") (pinfunction "2_2") (pintype "passive"))
      (node (ref "X1") (pin "4") (pinfunction "4_4") (pintype "passive"))
    )
    (net (code "24") (name "HAPTIC_EN{slash}1.4C") (class "Default")
      (node (ref "IC2") (pin "A1") (pinfunction "EN_A1") (pintype "bidirectional"))
    )
    (net (code "25") (name "HAPTIC_EN{slash}2.6A") (class "Default")
      (node (ref "U1") (pin "P$U1") (pinfunction "P0.12_P$U1") (pintype "bidirectional"))
    )
    (net (code "26") (name "IMU_INT1") (class "Default")
      (node (ref "IC3") (pin "5") (pinfunction "INT1_5") (pintype "bidirectional"))
      (node (ref "U1") (pin "P$N1") (pinfunction "P0.08_P$N1") (pintype "bidirectional"))
    )
    (net (code "27") (name "IMU_INT2") (class "Default")
      (node (ref "IC3") (pin "6") (pinfunction "INT2_6") (pintype "bidirectional"))
      (node (ref "U1") (pin "P$P2") (pinfunction "P1.08_P$P2") (pintype "bidirectional"))
    )
    (net (code "28") (name "LX1") (class "Default")
      (node (ref "IC9") (pin "B2") (pinfunction "SW1_1_B2") (pintype "bidirectional"))
      (node (ref "IC9") (pin "B3") (pinfunction "SW1_2_B3") (pintype "bidirectional"))
      (node (ref "L7") (pin "1") (pinfunction "1_1") (pintype "bidirectional"))
    )
    (net (code "29") (name "LX2") (class "Default")
      (node (ref "IC9") (pin "D2") (pinfunction "SW2_1_D2") (pintype "bidirectional"))
      (node (ref "IC9") (pin "D3") (pinfunction "SW2_2_D3") (pintype "bidirectional"))
      (node (ref "L7") (pin "2") (pinfunction "2_2") (pintype "bidirectional"))
    )
    (net (code "30") (name "MOSI{slash}1.5B") (class "Default")
      (node (ref "J1") (pin "14") (pinfunction "14_14") (pintype "bidirectional"))
    )
    (net (code "31") (name "MOSI{slash}2.2D") (class "Default")
      (node (ref "U1") (pin "P$B13") (pinfunction "P0.03/AIN1_P$B13") (pintype "bidirectional"))
    )
    (net (code "32") (name "N$21") (class "Default")
      (node (ref "R_PWR_EDP") (pin "2") (pinfunction "2_2") (pintype "bidirectional"))
    )
    (net (code "33") (name "Net-(ANT1-FEED)") (class "Default")
      (node (ref "ANT1") (pin "1") (pinfunction "FEED_1") (pintype "input"))
      (node (ref "C22") (pin "1") (pinfunction "1_1") (pintype "passive"))
      (node (ref "C4") (pin "1") (pinfunction "1_1") (pintype "passive"))
      (node (ref "L1") (pin "2") (pinfunction "2_2") (pintype "passive"))
    )
    (net (code "34") (name "Net-(D2-K)") (class "Default")
      (node (ref "C2-EP-DR") (pin "1") (pinfunction "1_1") (pintype "passive"))
      (node (ref "D2") (pin "1") (pinfunction "K_1") (pintype "bidirectional"))
      (node (ref "D4") (pin "2") (pinfunction "A_2") (pintype "bidirectional"))
    )
    (net (code "35") (name "Net-(D5-A)") (class "Default")
      (node (ref "C2-EP-DR") (pin "2") (pinfunction "2_2") (pintype "passive"))
      (node (ref "D5") (pin "2") (pinfunction "A_2") (pintype "bidirectional"))
      (node (ref "L5") (pin "1") (pinfunction "1_1") (pintype "passive"))
      (node (ref "Q3") (pin "3") (pinfunction "D_3") (pintype "bidirectional"))
    )
    (net (code "36") (name "Net-(EDP_C6-Pad2)") (class "Default")
      (node (ref "EDP_C6") (pin "2") (pinfunction "2_2") (pintype "passive"))
      (node (ref "J1") (pin "18") (pinfunction "18_18") (pintype "bidirectional"))
    )
    (net (code "37") (name "Net-(EDP_C7-Pad2)") (class "Default")
      (node (ref "EDP_C7") (pin "2") (pinfunction "2_2") (pintype "passive"))
      (node (ref "J1") (pin "19") (pinfunction "19_19") (pintype "bidirectional"))
    )
    (net (code "38") (name "Net-(EDP_C8-Pad2)") (class "Default")
      (node (ref "EDP_C8") (pin "2") (pinfunction "2_2") (pintype "passive"))
      (node (ref "J1") (pin "20") (pinfunction "20_20") (pintype "bidirectional"))
    )
    (net (code "39") (name "Net-(EDP_C9-Pad2)") (class "Default")
      (node (ref "EDP_C9") (pin "2") (pinfunction "2_2") (pintype "passive"))
      (node (ref "J1") (pin "21") (pinfunction "21_21") (pintype "bidirectional"))
    )
    (net (code "40") (name "Net-(EDP_C12-Pad2)") (class "Default")
      (node (ref "EDP_C12") (pin "2") (pinfunction "2_2") (pintype "passive"))
      (node (ref "J1") (pin "24") (pinfunction "24_24") (pintype "bidirectional"))
    )
    (net (code "41") (name "Net-(EPD_C1-Pad2)") (class "Default")
      (node (ref "EPD_C1") (pin "2") (pinfunction "2_2") (pintype "passive"))
      (node (ref "J1") (pin "5") (pinfunction "5_5") (pintype "bidirectional"))
    )
    (net (code "42") (name "Net-(EPD_C2-Pad2)") (class "Default")
      (node (ref "EPD_C2") (pin "2") (pinfunction "2_2") (pintype "passive"))
      (node (ref "J1") (pin "4") (pinfunction "4_4") (pintype "bidirectional"))
    )
    (net (code "43") (name "Net-(IC1-TS{slash}MR)") (class "Default")
      (node (ref "IC1") (pin "D1") (pinfunction "TS/MR_D1") (pintype "bidirectional"))
      (node (ref "R9") (pin "2") (pinfunction "2_2") (pintype "bidirectional"))
    )
    (net (code "44") (name "Net-(IC2-REG)") (class "Default")
      (node (ref "C32") (pin "2") (pinfunction "2_2") (pintype "passive"))
      (node (ref "IC2") (pin "A2") (pinfunction "REG_A2") (pintype "bidirectional"))
    )
    (net (code "45") (name "Net-(IC3-SDO)") (class "Default")
      (node (ref "IC3") (pin "1") (pinfunction "SDO_1") (pintype "bidirectional"))
      (node (ref "R3") (pin "2") (pinfunction "2_2") (pintype "bidirectional"))
    )
    (net (code "46") (name "Net-(IC9-SCL)") (class "Default")
      (node (ref "IC9") (pin "D1") (pinfunction "SCL_D1") (pintype "bidirectional"))
      (node (ref "R4") (pin "2") (pinfunction "2_2") (pintype "bidirectional"))
    )
    (net (code "47") (name "Net-(IC9-SDA)") (class "Default")
      (node (ref "IC9") (pin "E1") (pinfunction "SDA_E1") (pintype "bidirectional"))
      (node (ref "R2") (pin "2") (pinfunction "2_2") (pintype "bidirectional"))
    )
    (net (code "48") (name "Net-(J4-CC1)") (class "Default")
      (node (ref "J4") (pin "A5") (pinfunction "CC1_A5") (pintype "bidirectional"))
      (node (ref "R1_USB") (pin "2") (pinfunction "2_2") (pintype "bidirectional"))
    )
    (net (code "49") (name "Net-(J4-CC2)") (class "Default")
      (node (ref "J4") (pin "B5") (pinfunction "CC2_B5") (pintype "bidirectional"))
      (node (ref "R2_USB") (pin "1") (pinfunction "1_1") (pintype "bidirectional"))
    )
    (net (code "50") (name "Net-(L2-Pad2)") (class "Default")
      (node (ref "L2") (pin "2") (pinfunction "2_2") (pintype "passive"))
      (node (ref "L3") (pin "1") (pinfunction "1_1") (pintype "passive"))
    )
    (net (code "51") (name "Net-(R1_EP_DR-Pad1)") (class "Default")
      (node (ref "R1_EP_DR") (pin "1") (pinfunction "1_1") (pintype "bidirectional"))
      (node (ref "R_TYPE_SEL") (pin "2") (pinfunction "2_2") (pintype "bidirectional"))
      (node (ref "SJ1") (pin "2") (pinfunction "2_2") (pintype "passive"))
    )
    (net (code "52") (name "Net-(U1-ANT)") (class "Default")
      (node (ref "C3") (pin "1") (pinfunction "1_1") (pintype "passive"))
      (node (ref "L1") (pin "1") (pinfunction "1_1") (pintype "passive"))
      (node (ref "U1") (pin "P$H23") (pinfunction "ANT_P$H23") (pintype "bidirectional"))
    )
    (net (code "53") (name "Net-(U1-DCC)") (class "Default")
      (node (ref "L2") (pin "1") (pinfunction "1_1") (pintype "passive"))
      (node (ref "U1") (pin "P$B3") (pinfunction "DCC_P$B3") (pintype "output"))
    )
    (net (code "54") (name "Net-(U1-DEC1)") (class "Default")
      (node (ref "C5") (pin "1") (pinfunction "1_1") (pintype "passive"))
      (node (ref "U1") (pin "P$C1") (pinfunction "DEC1_P$C1") (pintype "power_in"))
    )
    (net (code "55") (name "Net-(U1-DEC2)") (class "Default")
      (node (ref "C13") (pin "1") (pinfunction "1_1") (pintype "passive"))
      (node (ref "U1") (pin "P$A18") (pinfunction "DEC2_P$A18") (pintype "bidirectional"))
    )
    (net (code "56") (name "Net-(U1-DEC3V3)") (class "Default")
      (node (ref "C20") (pin "1") (pinfunction "1_1") (pintype "passive"))
      (node (ref "U1") (pin "P$AC5") (pinfunction "DEC3V3_P$AC5") (pintype "bidirectional"))
    )
    (net (code "57") (name "Net-(U1-DEC5)") (class "Default")
      (node (ref "C9") (pin "1") (pinfunction "1_1") (pintype "passive"))
      (node (ref "U1") (pin "P$N24") (pinfunction "DEC5_P$N24") (pintype "bidirectional"))
    )
    (net (code "58") (name "Net-(U1-XC1)") (class "Default")
      (node (ref "C1") (pin "1") (pinfunction "1_1") (pintype "passive"))
      (node (ref "U1") (pin "P$B24") (pinfunction "XC1_P$B24") (pintype "input"))
      (node (ref "X1") (pin "1") (pinfunction "1_1") (pintype "passive"))
    )
    (net (code "59") (name "Net-(U1-XC2)") (class "Default")
      (node (ref "C2") (pin "1") (pinfunction "1_1") (pintype "passive"))
      (node (ref "U1") (pin "P$A23") (pinfunction "XC2_P$A23") (pintype "output"))
      (node (ref "X1") (pin "3") (pinfunction "3_3") (pintype "passive"))
    )
    (net (code "60") (name "OUT+") (class "Default")
      (node (ref "IC2") (pin "A3") (pinfunction "OUT+_A3") (pintype "bidirectional"))
      (node (ref "TP_OP") (pin "TP") (pinfunction "TP_TP") (pintype "input"))
    )
    (net (code "61") (name "OUT-") (class "Default")
      (node (ref "IC2") (pin "C3") (pinfunction "OUT-_C3") (pintype "bidirectional"))
      (node (ref "TP_ON") (pin "TP") (pinfunction "TP_TP") (pintype "input"))
    )
    (net (code "62") (name "P0.00{slash}XL1") (class "Default")
      (node (ref "C17") (pin "2") (pinfunction "2_2") (pintype "passive"))
      (node (ref "U1") (pin "P$D2") (pinfunction "P0.00/XL1_P$D2") (pintype "bidirectional"))
      (node (ref "X2") (pin "2") (pinfunction "2_2") (pintype "passive"))
    )
    (net (code "63") (name "P0.01{slash}XL2") (class "Default")
      (node (ref "C18") (pin "2") (pinfunction "2_2") (pintype "passive"))
      (node (ref "U1") (pin "P$F2") (pinfunction "P0.01/XL2_P$F2") (pintype "bidirectional"))
      (node (ref "X2") (pin "1") (pinfunction "1_1") (pintype "passive"))
    )
    (net (code "64") (name "P0.04") (class "Default")
      (node (ref "U1") (pin "P$J1") (pinfunction "P0.04/AIN2_P$J1") (pintype "bidirectional"))
    )
    (net (code "65") (name "P0.09") (class "Default")
      (node (ref "U1") (pin "P$L24") (pinfunction "P0.09/NFC1_P$L24") (pintype "bidirectional"))
    )
    (net (code "66") (name "P0.13{slash}1.5D") (class "Default")
      (node (ref "C30") (pin "2") (pinfunction "2_2") (pintype "passive"))
      (node (ref "R5") (pin "1") (pinfunction "1_1") (pintype "bidirectional"))
      (node (ref "SW_UP") (pin "2") (pinfunction "2_2") (pintype "passive"))
    )
    (net (code "67") (name "P0.13{slash}2.6C") (class "Default")
      (node (ref "U1") (pin "P$AD8") (pinfunction "P0.13_P$AD8") (pintype "bidirectional"))
    )
    (net (code "68") (name "P0.14{slash}1.5D") (class "Default")
      (node (ref "C31") (pin "2") (pinfunction "2_2") (pintype "passive"))
      (node (ref "R8") (pin "1") (pinfunction "1_1") (pintype "bidirectional"))
      (node (ref "SW_ENT") (pin "2") (pinfunction "2_2") (pintype "passive"))
    )
    (net (code "69") (name "P0.14{slash}2.7C") (class "Default")
      (node (ref "U1") (pin "P$AC9") (pinfunction "P0.14_P$AC9") (pintype "bidirectional"))
    )
    (net (code "70") (name "P0.19") (class "Default")
      (node (ref "U1") (pin "P$AC15") (pinfunction "P0.19_P$AC15") (pintype "bidirectional"))
    )
    (net (code "71") (name "P0.20") (class "Default")
      (node (ref "U1") (pin "P$AD16") (pinfunction "P0.20_P$AD16") (pintype "bidirectional"))
    )
    (net (code "72") (name "P0.21") (class "Default")
      (node (ref "U1") (pin "P$AC17") (pinfunction "P0.21_P$AC17") (pintype "bidirectional"))
    )
    (net (code "73") (name "P0.22") (class "Default")
      (node (ref "U1") (pin "P$AD18") (pinfunction "P0.22_P$AD18") (pintype "bidirectional"))
    )
    (net (code "74") (name "P0.23") (class "Default")
      (node (ref "U1") (pin "P$AC19") (pinfunction "P0.23_P$AC19") (pintype "bidirectional"))
    )
    (net (code "75") (name "P0.24") (class "Default")
      (node (ref "U1") (pin "P$AD20") (pinfunction "P0.24_P$AD20") (pintype "bidirectional"))
    )
    (net (code "76") (name "P0.25") (class "Default")
      (node (ref "U1") (pin "P$AC21") (pinfunction "P0.25_P$AC21") (pintype "bidirectional"))
    )
    (net (code "77") (name "P0.26") (class "Default")
      (node (ref "U1") (pin "P$G1") (pinfunction "P0.26_P$G1") (pintype "bidirectional"))
    )
    (net (code "78") (name "P0.27") (class "Default")
      (node (ref "U1") (pin "P$H2") (pinfunction "P0.27_P$H2") (pintype "bidirectional"))
    )
    (net (code "79") (name "P0.28") (class "Default")
      (node (ref "U1") (pin "P$B11") (pinfunction "P0.28/AIN4_P$B11") (pintype "bidirectional"))
    )
    (net (code "80") (name "P0.29") (class "Default")
      (node (ref "U1") (pin "P$A10") (pinfunction "P0.29/AIN5_P$A10") (pintype "bidirectional"))
    )
    (net (code "81") (name "P0.30") (class "Default")
      (node (ref "U1") (pin "P$B9") (pinfunction "P0.30/AIN6_P$B9") (pintype "bidirectional"))
    )
    (net (code "82") (name "P0.31") (class "Default")
      (node (ref "U1") (pin "P$A8") (pinfunction "P0.31/AIN7_P$A8") (pintype "bidirectional"))
    )
    (net (code "83") (name "P1.01{slash}1.6C") (class "Default")
      (node (ref "Q1") (pin "1") (pinfunction "G_1") (pintype "bidirectional"))
      (node (ref "R_PWR_EDP") (pin "1") (pinfunction "1_1") (pintype "bidirectional"))
    )
    (net (code "84") (name "P1.01{slash}2.4B") (class "Default")
      (node (ref "U1") (pin "P$Y23") (pinfunction "P1.01_P$Y23") (pintype "bidirectional"))
    )
    (net (code "85") (name "P1.02{slash}1.6C") (class "Default")
      (node (ref "C29") (pin "2") (pinfunction "2_2") (pintype "passive"))
      (node (ref "R7") (pin "1") (pinfunction "1_1") (pintype "bidirectional"))
      (node (ref "SW_DN") (pin "2") (pinfunction "2_2") (pintype "passive"))
    )
    (net (code "86") (name "P1.02{slash}2.8C") (class "Default")
      (node (ref "U1") (pin "P$W24") (pinfunction "P1.02_P$W24") (pintype "bidirectional"))
    )
    (net (code "87") (name "P1.03") (class "Default")
      (node (ref "U1") (pin "P$V23") (pinfunction "P1.03_P$V23") (pintype "bidirectional"))
    )
    (net (code "88") (name "P1.04") (class "Default")
      (node (ref "U1") (pin "P$U24") (pinfunction "P1.04_P$U24") (pintype "bidirectional"))
    )
    (net (code "89") (name "P1.05") (class "Default")
      (node (ref "U1") (pin "P$T23") (pinfunction "P1.05_P$T23") (pintype "bidirectional"))
    )
    (net (code "90") (name "P1.06") (class "Default")
      (node (ref "U1") (pin "P$R24") (pinfunction "P1.06_P$R24") (pintype "bidirectional"))
    )
    (net (code "91") (name "P1.07") (class "Default")
      (node (ref "U1") (pin "P$P23") (pinfunction "P1.07_P$P23") (pintype "bidirectional"))
    )
    (net (code "92") (name "P1.09") (class "Default")
      (node (ref "U1") (pin "P$R1") (pinfunction "P1.09_P$R1") (pintype "bidirectional"))
    )
    (net (code "93") (name "P1.10") (class "Default")
      (node (ref "U1") (pin "P$A20") (pinfunction "P1.10_P$A20") (pintype "bidirectional"))
    )
    (net (code "94") (name "P1.11") (class "Default")
      (node (ref "U1") (pin "P$B19") (pinfunction "P1.11_P$B19") (pintype "bidirectional"))
    )
    (net (code "95") (name "P1.12") (class "Default")
      (node (ref "U1") (pin "P$B17") (pinfunction "P1.12_P$B17") (pintype "bidirectional"))
    )
    (net (code "96") (name "P1.13") (class "Default")
      (node (ref "U1") (pin "P$A16") (pinfunction "P1.13_P$A16") (pintype "bidirectional"))
    )
    (net (code "97") (name "P1.14") (class "Default")
      (node (ref "U1") (pin "P$B15") (pinfunction "P1.14_P$B15") (pintype "bidirectional"))
    )
    (net (code "98") (name "P1.15") (class "Default")
      (node (ref "U1") (pin "P$A14") (pinfunction "P1.15_P$A14") (pintype "bidirectional"))
    )
    (net (code "99") (name "PMIC_INT") (class "Default")
      (node (ref "IC1") (pin "A1") (pinfunction "~{INT}_A1") (pintype "bidirectional"))
      (node (ref "U1") (pin "P$T2") (pinfunction "P0.11_P$T2") (pintype "bidirectional"))
    )
    (net (code "100") (name "PREVGH") (class "Default")
      (node (ref "D5") (pin "1") (pinfunction "K_1") (pintype "bidirectional"))
      (node (ref "EDP_C10") (pin "2") (pinfunction "2_2") (pintype "passive"))
      (node (ref "J1") (pin "22") (pinfunction "22_22") (pintype "bidirectional"))
    )
    (net (code "101") (name "PREVGL") (class "Default")
      (node (ref "D2") (pin "2") (pinfunction "A_2") (pintype "bidirectional"))
      (node (ref "EDP_C11") (pin "2") (pinfunction "2_2") (pintype "passive"))
      (node (ref "J1") (pin "23") (pinfunction "23_23") (pintype "bidirectional"))
    )
    (net (code "102") (name "RESE") (class "Default")
      (node (ref "J1") (pin "3") (pinfunction "3_3") (pintype "bidirectional"))
      (node (ref "Q3") (pin "2") (pinfunction "S_2") (pintype "bidirectional"))
      (node (ref "R1_EP_DR") (pin "2") (pinfunction "2_2") (pintype "bidirectional"))
    )
    (net (code "103") (name "RESET") (class "Default")
      (node (ref "J2") (pin "6") (pinfunction "6_6") (pintype "bidirectional"))
      (node (ref "TP_RESET") (pin "TP") (pinfunction "TP_TP") (pintype "input"))
      (node (ref "U1") (pin "P$AC13") (pinfunction "P0.18/RESET_P$AC13") (pintype "bidirectional"))
    )
    (net (code "104") (name "SCK{slash}1.5B") (class "Default")
      (node (ref "J1") (pin "13") (pinfunction "13_13") (pintype "bidirectional"))
    )
    (net (code "105") (name "SCK{slash}2.2D") (class "Default")
      (node (ref "U1") (pin "P$A12") (pinfunction "P0.02/AIN0_P$A12") (pintype "bidirectional"))
    )
    (net (code "106") (name "SCL{slash}1.4C") (class "Default")
      (node (ref "IC2") (pin "C1") (pinfunction "SCL_C1") (pintype "bidirectional"))
      (node (ref "U3") (pin "7") (pinfunction "SCL_7") (pintype "input"))
    )
    (net (code "107") (name "SCL{slash}2.4C") (class "Default")
      (node (ref "IC1") (pin "B1") (pinfunction "SCL_B1") (pintype "bidirectional"))
      (node (ref "IC3") (pin "12") (pinfunction "SCX_12") (pintype "bidirectional"))
      (node (ref "R17") (pin "2") (pinfunction "2_2") (pintype "bidirectional"))
      (node (ref "R4") (pin "1") (pinfunction "1_1") (pintype "bidirectional"))
      (node (ref "TP_SCL") (pin "TP") (pinfunction "TP_TP") (pintype "input"))
      (node (ref "U1") (pin "P$M2") (pinfunction "P0.07_P$M2") (pintype "bidirectional"))
    )
    (net (code "108") (name "SDA{slash}1.4C") (class "Default")
      (node (ref "IC2") (pin "B2") (pinfunction "SDA_B2") (pintype "bidirectional"))
      (node (ref "U3") (pin "8") (pinfunction "SDA_8") (pintype "bidirectional"))
    )
    (net (code "109") (name "SDA{slash}2.4C") (class "Default")
      (node (ref "IC1") (pin "C1") (pinfunction "SDA_C1") (pintype "bidirectional"))
      (node (ref "IC3") (pin "2") (pinfunction "SDX_2") (pintype "bidirectional"))
      (node (ref "R18") (pin "2") (pinfunction "2_2") (pintype "bidirectional"))
      (node (ref "R2") (pin "1") (pinfunction "1_1") (pintype "bidirectional"))
      (node (ref "TP_SDA") (pin "TP") (pinfunction "TP_TP") (pintype "input"))
      (node (ref "U1") (pin "P$L1") (pinfunction "P0.06_P$L1") (pintype "bidirectional"))
    )
    (net (code "110") (name "SWDCLK") (class "Default")
      (node (ref "J2") (pin "4") (pinfunction "4_4") (pintype "bidirectional"))
      (node (ref "TP_SWDCLK") (pin "TP") (pinfunction "TP_TP") (pintype "input"))
      (node (ref "U1") (pin "P$AA24") (pinfunction "SWDCLK_P$AA24") (pintype "input"))
    )
    (net (code "111") (name "SWDIO") (class "Default")
      (node (ref "J2") (pin "2") (pinfunction "2_2") (pintype "bidirectional"))
      (node (ref "TP_SWDIO") (pin "TP") (pinfunction "TP_TP") (pintype "input"))
      (node (ref "U1") (pin "P$AC24") (pinfunction "SWDIO_P$AC24") (pintype "bidirectional"))
    )
    (net (code "112") (name "SWO") (class "Default")
      (node (ref "TP_SWO") (pin "TP") (pinfunction "TP_TP") (pintype "input"))
      (node (ref "U1") (pin "P$AD22") (pinfunction "P1.00_P$AD22") (pintype "bidirectional"))
    )
    (net (code "113") (name "VBAT{slash}1.2A") (class "Default")
      (node (ref "C27") (pin "2") (pinfunction "2_2") (pintype "passive"))
      (node (ref "TP1") (pin "TP") (pinfunction "TP_TP") (pintype "input"))
      (node (ref "U3") (pin "2") (pinfunction "CELL_2") (pintype "power_in"))
      (node (ref "U3") (pin "3") (pinfunction "VDD_3") (pintype "power_in"))
    )
    (net (code "114") (name "VBAT{slash}2.5C") (class "Default")
      (node (ref "C37") (pin "2") (pinfunction "2_2") (pintype "passive"))
      (node (ref "IC1") (pin "C2") (pinfunction "BAT_C2") (pintype "bidirectional"))
    )
    (net (code "115") (name "VBUS{slash}1.5D") (class "Default")
      (node (ref "C42") (pin "1") (pinfunction "1_1") (pintype "passive"))
      (node (ref "C43") (pin "1") (pinfunction "1_1") (pintype "passive"))
      (node (ref "D3") (pin "5") (pinfunction "VBUS_5") (pintype "bidirectional"))
      (node (ref "J4") (pin "A4_B9") (pinfunction "VBUS_A4_B9") (pintype "power_in"))
      (node (ref "J4") (pin "A9_B4") (pinfunction "VBUS_A9_B4") (pintype "power_in"))
    )
    (net (code "116") (name "VBUS{slash}2.6D") (class "Default")
      (node (ref "C21") (pin "1") (pinfunction "1_1") (pintype "passive"))
      (node (ref "C38") (pin "2") (pinfunction "2_2") (pintype "passive"))
      (node (ref "IC1") (pin "A2") (pinfunction "IN_A2") (pintype "bidirectional"))
      (node (ref "U1") (pin "P$AD2") (pinfunction "VBUS_P$AD2") (pintype "power_in"))
    )
    (net (code "117") (name "VREG") (class "Default")
      (node (ref "C23") (pin "1") (pinfunction "1_1") (pintype "passive"))
      (node (ref "C24") (pin "2") (pinfunction "2_2") (pintype "passive"))
      (node (ref "C39") (pin "1") (pinfunction "1_1") (pintype "passive"))
      (node (ref "IC1") (pin "B2") (pinfunction "SYS_B2") (pintype "bidirectional"))
      (node (ref "IC9") (pin "A1") (pinfunction "EN_A1") (pintype "bidirectional"))
      (node (ref "IC9") (pin "A2") (pinfunction "VIN_1_A2") (pintype "bidirectional"))
      (node (ref "IC9") (pin "A3") (pinfunction "VIN_2_A3") (pintype "bidirectional"))
      (node (ref "TP_VREG") (pin "TP") (pinfunction "TP_TP") (pintype "input"))
    )
    (net (code "118") (name "unconnected-(ANT1-NC-Pad2)") (class "Default")
      (node (ref "ANT1") (pin "2") (pinfunction "NC_2") (pintype "no_connect"))
    )
    (net (code "119") (name "unconnected-(IC3-ASCL-Pad11)") (class "Default")
      (node (ref "IC3") (pin "11") (pinfunction "ASCL_11") (pintype "bidirectional"))
    )
    (net (code "120") (name "unconnected-(IC3-ASDA-Pad4)") (class "Default")
      (node (ref "IC3") (pin "4") (pinfunction "ASDA_4") (pintype "bidirectional"))
    )
    (net (code "121") (name "unconnected-(J1-Pad1)") (class "Default")
      (node (ref "J1") (pin "1") (pinfunction "1_1") (pintype "bidirectional"))
    )
    (net (code "122") (name "unconnected-(J1-Pad6)") (class "Default")
      (node (ref "J1") (pin "6") (pinfunction "6_6") (pintype "bidirectional"))
    )
    (net (code "123") (name "unconnected-(J1-Pad7)") (class "Default")
      (node (ref "J1") (pin "7") (pinfunction "7_7") (pintype "bidirectional"))
    )
    (net (code "124") (name "unconnected-(J4-SBU1-PadA8)") (class "Default")
      (node (ref "J4") (pin "A8") (pinfunction "SBU1_A8") (pintype "bidirectional"))
    )
    (net (code "125") (name "unconnected-(J4-SBU2-PadB8)") (class "Default")
      (node (ref "J4") (pin "B8") (pinfunction "SBU2_B8") (pintype "bidirectional"))
    )
    (net (code "126") (name "unconnected-(U1-DCCH-PadP$AB2)") (class "Default")
      (node (ref "U1") (pin "P$AB2") (pinfunction "DCCH_P$AB2") (pintype "bidirectional"))
    )
  )
)
